# MiniPrinter1_0.net
KiCad netlist of a schematic drawn in Altium Designer
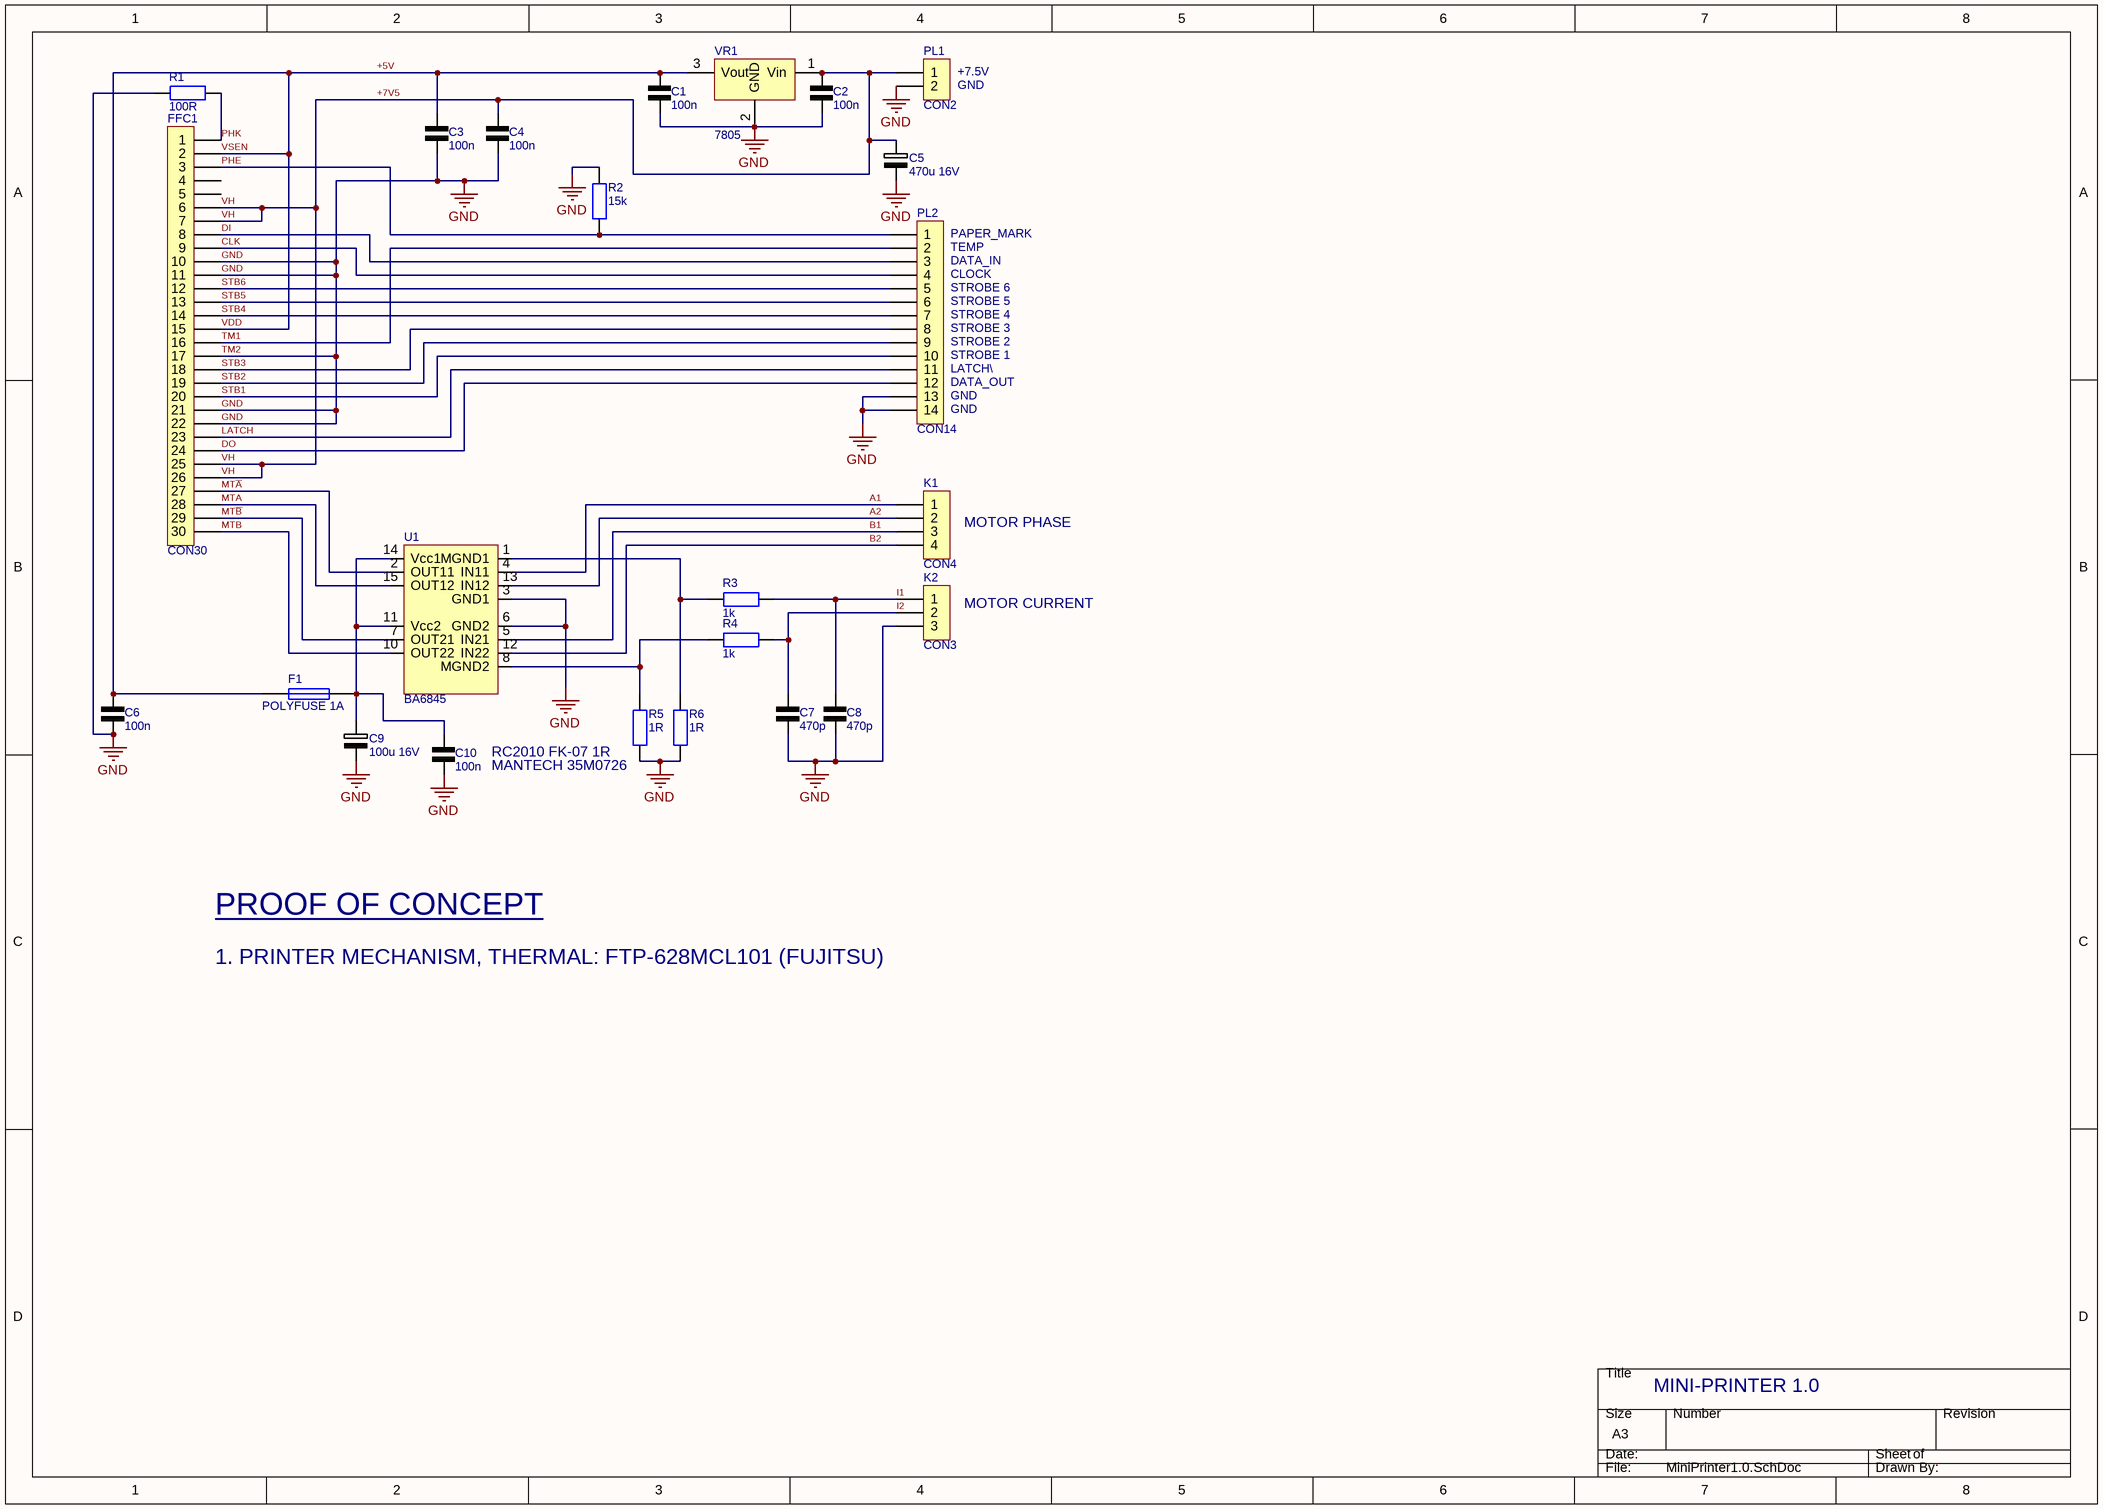
[diagram p0: MiniPrinter1.0.SchDoc]

(export (version "E")
  (design (tool "Eeschema 10.0.6"))
  (components
    (comp (ref "C1")
      (value "100n")
      (footprint "SM 0805")
      (libsource (lib "SCHEMATIC SYMBOLS") (part "CAPACITOR"))
    )
    (comp (ref "C2")
      (value "100n")
      (footprint "SM 0805")
      (libsource (lib "SCHEMATIC SYMBOLS") (part "CAPACITOR"))
    )
    (comp (ref "C3")
      (value "100n")
      (footprint "SM 0805")
      (libsource (lib "SCHEMATIC SYMBOLS") (part "CAPACITOR"))
    )
    (comp (ref "C4")
      (value "100n")
      (footprint "SM 0805")
      (libsource (lib "SCHEMATIC SYMBOLS") (part "CAPACITOR"))
    )
    (comp (ref "C5")
      (value "470u 16V")
      (footprint "CAP RADIAL 5/13")
      (libsource (lib "SCHEMATIC SYMBOLS") (part "POL_CAP"))
    )
    (comp (ref "C6")
      (value "100n")
      (footprint "SM 0805")
      (libsource (lib "SCHEMATIC SYMBOLS") (part "CAPACITOR"))
    )
    (comp (ref "C7")
      (value "470p")
      (footprint "SM 0603")
      (libsource (lib "SCHEMATIC SYMBOLS") (part "CAPACITOR"))
    )
    (comp (ref "C8")
      (value "470p")
      (footprint "SM 0603")
      (libsource (lib "SCHEMATIC SYMBOLS") (part "CAPACITOR"))
    )
    (comp (ref "C9")
      (value "100u 16V")
      (footprint "CAP RADIAL 2.5/6")
      (libsource (lib "SCHEMATIC SYMBOLS") (part "POL_CAP"))
    )
    (comp (ref "C10")
      (value "100n")
      (footprint "SM 0805")
      (libsource (lib "SCHEMATIC SYMBOLS") (part "CAPACITOR"))
    )
    (comp (ref "F1")
      (value "POLYFUSE 1A")
      (footprint "MSF110")
      (description "Fuse")
      (libsource (lib "SCHEMATIC SYMBOLS") (part "FUSE"))
    )
    (comp (ref "FFC1")
      (value "CON30")
      (footprint "FFC30-1.0-TH-ZIF")
      (libsource (lib "SCHEMATIC SYMBOLS") (part "CON30"))
    )
    (comp (ref "K1")
      (value "CON4")
      (footprint "SIL4")
      (description "4 Way Connector")
      (libsource (lib "SCHEMATIC SYMBOLS") (part "CON4"))
    )
    (comp (ref "K2")
      (value "CON3")
      (footprint "SIL3")
      (description "3 Way Connector")
      (libsource (lib "SCHEMATIC SYMBOLS") (part "CON3"))
    )
    (comp (ref "PL1")
      (value "CON2")
      (footprint "DG127-5.0-2")
      (description "2 Way connector")
      (libsource (lib "SCHEMATIC SYMBOLS") (part "CON2"))
    )
    (comp (ref "PL2")
      (value "CON14")
      (footprint "SIL14")
      (description "14 Way Connector")
      (libsource (lib "SCHEMATIC SYMBOLS") (part "CON14"))
    )
    (comp (ref "R1") (value "100R") (footprint "SM 0805") (libsource (lib "SCHEMATIC SYMBOLS") (part "RES")))
    (comp (ref "R2") (value "15k") (footprint "SM 0805") (libsource (lib "SCHEMATIC SYMBOLS") (part "RES")))
    (comp (ref "R3") (value "1k") (footprint "SM 1206") (libsource (lib "SCHEMATIC SYMBOLS") (part "RES")))
    (comp (ref "R4") (value "1k") (footprint "SM 1206") (libsource (lib "SCHEMATIC SYMBOLS") (part "RES")))
    (comp (ref "R5") (value "1R") (footprint "RES 1/4W H") (libsource (lib "SCHEMATIC SYMBOLS") (part "RES")))
    (comp (ref "R6") (value "1R") (footprint "RES 1/4W H") (libsource (lib "SCHEMATIC SYMBOLS") (part "RES")))
    (comp (ref "U1")
      (value "BA6845")
      (footprint "SSOP-A16 (ROHM)")
      (libsource (lib "SCHEMATIC SYMBOLS") (part "BA6845"))
    )
    (comp (ref "VR1")
      (value "7805")
      (footprint "TO-220V")
      (description "Fixed voltage regulator")
      (libsource (lib "SCHEMATIC SYMBOLS") (part "REG 78XX"))
    )
  )
  (nets
    (net (code "1") (name "/+5V") (class "Default")
      (node (ref "C1") (pin "1") (pinfunction "1_1") (pintype "passive"))
      (node (ref "C3") (pin "1") (pinfunction "1_1") (pintype "passive"))
      (node (ref "C6") (pin "1") (pinfunction "1_1") (pintype "passive"))
      (node (ref "F1") (pin "1") (pinfunction "1_1") (pintype "passive"))
      (node (ref "FFC1") (pin "15") (pinfunction "15_15") (pintype "passive"))
      (node (ref "FFC1") (pin "2") (pinfunction "2_2") (pintype "passive"))
      (node (ref "VR1") (pin "3") (pinfunction "Vout_3") (pintype "passive"))
    )
    (net (code "2") (name "/+7V5") (class "Default")
      (node (ref "C2") (pin "1") (pinfunction "1_1") (pintype "passive"))
      (node (ref "C4") (pin "1") (pinfunction "1_1") (pintype "passive"))
      (node (ref "C5") (pin "1") (pinfunction "1_1") (pintype "passive"))
      (node (ref "FFC1") (pin "25") (pinfunction "25_25") (pintype "passive"))
      (node (ref "FFC1") (pin "26") (pinfunction "26_26") (pintype "passive"))
      (node (ref "FFC1") (pin "6") (pinfunction "6_6") (pintype "passive"))
      (node (ref "FFC1") (pin "7") (pinfunction "7_7") (pintype "passive"))
      (node (ref "PL1") (pin "1") (pinfunction "1_1") (pintype "passive"))
      (node (ref "VR1") (pin "1") (pinfunction "Vin_1") (pintype "passive"))
    )
    (net (code "3") (name "/A1") (class "Default")
      (node (ref "K1") (pin "1") (pinfunction "1_1") (pintype "passive"))
      (node (ref "U1") (pin "4") (pinfunction "IN11_4") (pintype "passive"))
    )
    (net (code "4") (name "/A2") (class "Default")
      (node (ref "K1") (pin "2") (pinfunction "2_2") (pintype "passive"))
      (node (ref "U1") (pin "13") (pinfunction "IN12_13") (pintype "passive"))
    )
    (net (code "5") (name "/B1") (class "Default")
      (node (ref "K1") (pin "3") (pinfunction "3_3") (pintype "passive"))
      (node (ref "U1") (pin "5") (pinfunction "IN21_5") (pintype "passive"))
    )
    (net (code "6") (name "/B2") (class "Default")
      (node (ref "K1") (pin "4") (pinfunction "4_4") (pintype "passive"))
      (node (ref "U1") (pin "12") (pinfunction "IN22_12") (pintype "passive"))
    )
    (net (code "7") (name "/CLK") (class "Default")
      (node (ref "FFC1") (pin "9") (pinfunction "9_9") (pintype "passive"))
      (node (ref "PL2") (pin "4") (pinfunction "4_4") (pintype "passive"))
    )
    (net (code "8") (name "/DI") (class "Default")
      (node (ref "FFC1") (pin "8") (pinfunction "8_8") (pintype "passive"))
      (node (ref "PL2") (pin "3") (pinfunction "3_3") (pintype "passive"))
    )
    (net (code "9") (name "/DO") (class "Default")
      (node (ref "FFC1") (pin "24") (pinfunction "24_24") (pintype "passive"))
      (node (ref "PL2") (pin "12") (pinfunction "12_12") (pintype "passive"))
    )
    (net (code "10") (name "/I1") (class "Default")
      (node (ref "C8") (pin "1") (pinfunction "1_1") (pintype "passive"))
      (node (ref "K2") (pin "1") (pinfunction "1_1") (pintype "passive"))
      (node (ref "R3") (pin "2") (pinfunction "2_2") (pintype "passive"))
    )
    (net (code "11") (name "/I2") (class "Default")
      (node (ref "C7") (pin "1") (pinfunction "1_1") (pintype "passive"))
      (node (ref "K2") (pin "2") (pinfunction "2_2") (pintype "passive"))
      (node (ref "R4") (pin "2") (pinfunction "2_2") (pintype "passive"))
    )
    (net (code "12") (name "/LATCH") (class "Default")
      (node (ref "FFC1") (pin "23") (pinfunction "23_23") (pintype "passive"))
      (node (ref "PL2") (pin "11") (pinfunction "11_11") (pintype "passive"))
    )
    (net (code "13") (name "/MTA") (class "Default")
      (node (ref "FFC1") (pin "28") (pinfunction "28_28") (pintype "passive"))
      (node (ref "U1") (pin "15") (pinfunction "OUT12_15") (pintype "passive"))
    )
    (net (code "14") (name "/MTB") (class "Default")
      (node (ref "FFC1") (pin "30") (pinfunction "30_30") (pintype "passive"))
      (node (ref "U1") (pin "10") (pinfunction "OUT22_10") (pintype "passive"))
    )
    (net (code "15") (name "/MT~{A}") (class "Default")
      (node (ref "FFC1") (pin "27") (pinfunction "27_27") (pintype "passive"))
      (node (ref "U1") (pin "2") (pinfunction "OUT11_2") (pintype "passive"))
    )
    (net (code "16") (name "/MT~{B}") (class "Default")
      (node (ref "FFC1") (pin "29") (pinfunction "29_29") (pintype "passive"))
      (node (ref "U1") (pin "7") (pinfunction "OUT21_7") (pintype "passive"))
    )
    (net (code "17") (name "/PHE") (class "Default")
      (node (ref "FFC1") (pin "3") (pinfunction "3_3") (pintype "passive"))
      (node (ref "PL2") (pin "1") (pinfunction "1_1") (pintype "passive"))
      (node (ref "R2") (pin "1") (pinfunction "1_1") (pintype "passive"))
    )
    (net (code "18") (name "/PHK") (class "Default")
      (node (ref "FFC1") (pin "1") (pinfunction "1_1") (pintype "passive"))
      (node (ref "R1") (pin "1") (pinfunction "1_1") (pintype "passive"))
    )
    (net (code "19") (name "/STB1") (class "Default")
      (node (ref "FFC1") (pin "20") (pinfunction "20_20") (pintype "passive"))
      (node (ref "PL2") (pin "10") (pinfunction "10_10") (pintype "passive"))
    )
    (net (code "20") (name "/STB2") (class "Default")
      (node (ref "FFC1") (pin "19") (pinfunction "19_19") (pintype "passive"))
      (node (ref "PL2") (pin "9") (pinfunction "9_9") (pintype "passive"))
    )
    (net (code "21") (name "/STB3") (class "Default")
      (node (ref "FFC1") (pin "18") (pinfunction "18_18") (pintype "passive"))
      (node (ref "PL2") (pin "8") (pinfunction "8_8") (pintype "passive"))
    )
    (net (code "22") (name "/STB4") (class "Default")
      (node (ref "FFC1") (pin "14") (pinfunction "14_14") (pintype "passive"))
      (node (ref "PL2") (pin "7") (pinfunction "7_7") (pintype "passive"))
    )
    (net (code "23") (name "/STB5") (class "Default")
      (node (ref "FFC1") (pin "13") (pinfunction "13_13") (pintype "passive"))
      (node (ref "PL2") (pin "6") (pinfunction "6_6") (pintype "passive"))
    )
    (net (code "24") (name "/STB6") (class "Default")
      (node (ref "FFC1") (pin "12") (pinfunction "12_12") (pintype "passive"))
      (node (ref "PL2") (pin "5") (pinfunction "5_5") (pintype "passive"))
    )
    (net (code "25") (name "/TM1") (class "Default")
      (node (ref "FFC1") (pin "16") (pinfunction "16_16") (pintype "passive"))
      (node (ref "PL2") (pin "2") (pinfunction "2_2") (pintype "passive"))
    )
    (net (code "26") (name "GND") (class "Default")
      (node (ref "C1") (pin "2") (pinfunction "2_2") (pintype "passive"))
      (node (ref "C10") (pin "2") (pinfunction "2_2") (pintype "passive"))
      (node (ref "C2") (pin "2") (pinfunction "2_2") (pintype "passive"))
      (node (ref "C3") (pin "2") (pinfunction "2_2") (pintype "passive"))
      (node (ref "C4") (pin "2") (pinfunction "2_2") (pintype "passive"))
      (node (ref "C5") (pin "2") (pinfunction "2_2") (pintype "passive"))
      (node (ref "C6") (pin "2") (pinfunction "2_2") (pintype "passive"))
      (node (ref "C7") (pin "2") (pinfunction "2_2") (pintype "passive"))
      (node (ref "C8") (pin "2") (pinfunction "2_2") (pintype "passive"))
      (node (ref "C9") (pin "2") (pinfunction "2_2") (pintype "passive"))
      (node (ref "FFC1") (pin "10") (pinfunction "10_10") (pintype "passive"))
      (node (ref "FFC1") (pin "11") (pinfunction "11_11") (pintype "passive"))
      (node (ref "FFC1") (pin "17") (pinfunction "17_17") (pintype "passive"))
      (node (ref "FFC1") (pin "21") (pinfunction "21_21") (pintype "passive"))
      (node (ref "FFC1") (pin "22") (pinfunction "22_22") (pintype "passive"))
      (node (ref "K2") (pin "3") (pinfunction "3_3") (pintype "passive"))
      (node (ref "PL1") (pin "2") (pinfunction "2_2") (pintype "passive"))
      (node (ref "PL2") (pin "13") (pinfunction "13_13") (pintype "passive"))
      (node (ref "PL2") (pin "14") (pinfunction "14_14") (pintype "passive"))
      (node (ref "R1") (pin "2") (pinfunction "2_2") (pintype "passive"))
      (node (ref "R2") (pin "2") (pinfunction "2_2") (pintype "passive"))
      (node (ref "R5") (pin "1") (pinfunction "1_1") (pintype "passive"))
      (node (ref "R6") (pin "1") (pinfunction "1_1") (pintype "passive"))
      (node (ref "U1") (pin "3") (pinfunction "GND1_3") (pintype "passive"))
      (node (ref "U1") (pin "6") (pinfunction "GND2_6") (pintype "passive"))
      (node (ref "VR1") (pin "2") (pinfunction "GND_2") (pintype "passive"))
    )
    (net (code "27") (name "Net-(U1-MGND1)") (class "Default")
      (node (ref "R3") (pin "1") (pinfunction "1_1") (pintype "passive"))
      (node (ref "R6") (pin "2") (pinfunction "2_2") (pintype "passive"))
      (node (ref "U1") (pin "1") (pinfunction "MGND1_1") (pintype "passive"))
    )
    (net (code "28") (name "Net-(U1-MGND2)") (class "Default")
      (node (ref "R4") (pin "1") (pinfunction "1_1") (pintype "passive"))
      (node (ref "R5") (pin "2") (pinfunction "2_2") (pintype "passive"))
      (node (ref "U1") (pin "8") (pinfunction "MGND2_8") (pintype "passive"))
    )
    (net (code "29") (name "Net-(U1-Vcc1)") (class "Default")
      (node (ref "C10") (pin "1") (pinfunction "1_1") (pintype "passive"))
      (node (ref "C9") (pin "1") (pinfunction "1_1") (pintype "passive"))
      (node (ref "F1") (pin "2") (pinfunction "2_2") (pintype "passive"))
      (node (ref "U1") (pin "11") (pinfunction "Vcc2_11") (pintype "passive"))
      (node (ref "U1") (pin "14") (pinfunction "Vcc1_14") (pintype "passive"))
    )
    (net (code "30") (name "unconnected-(FFC1-Pad4)") (class "Default")
      (node (ref "FFC1") (pin "4") (pinfunction "4_4") (pintype "passive"))
    )
    (net (code "31") (name "unconnected-(FFC1-Pad5)") (class "Default")
      (node (ref "FFC1") (pin "5") (pinfunction "5_5") (pintype "passive"))
    )
    (net (code "32") (name "unconnected-(U1-NC-Pad9)") (class "Default")
      (node (ref "U1") (pin "9") (pinfunction "NC_9") (pintype "passive"))
    )
    (net (code "33") (name "unconnected-(U1-NC-Pad16)") (class "Default")
      (node (ref "U1") (pin "16") (pinfunction "NC_16") (pintype "passive"))
    )
  )
)
